# Headstage_Mainboard.net
KiCad netlist of a schematic drawn in Altium Designer
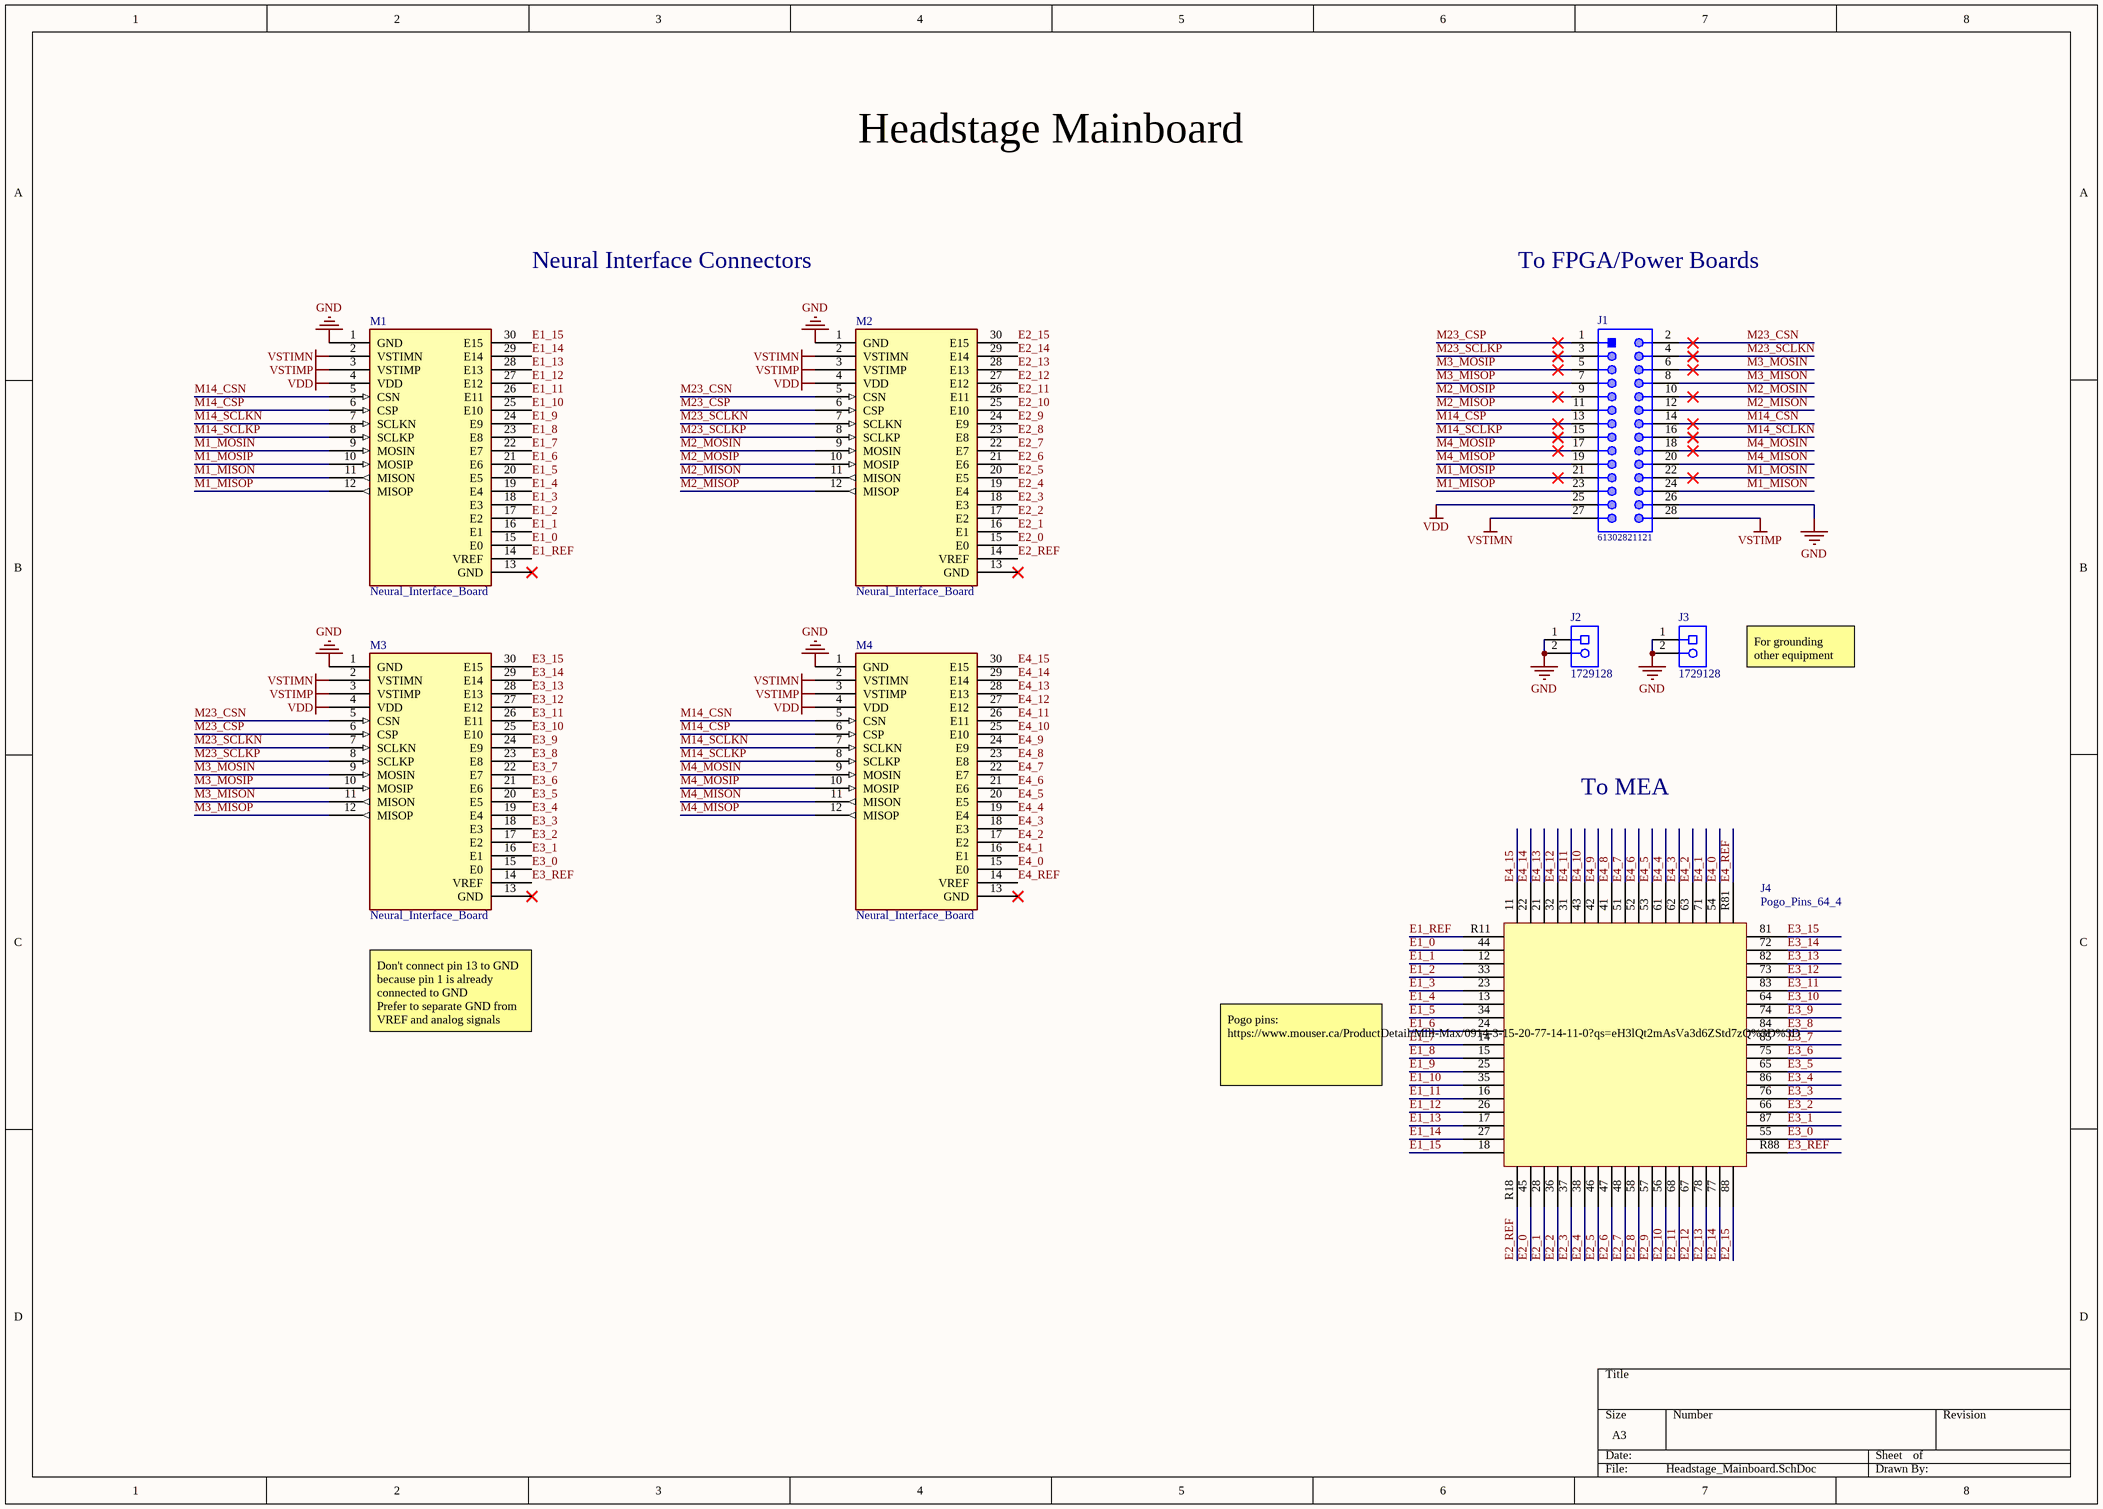
[diagram p0: Headstage_Mainboard.SchDoc]

(export (version "E")
  (design (tool "Eeschema 10.0.6"))
  (components
    (comp (ref "J1")
      (value "61302821121")
      (footprint "61302821121")
      (description "THT Vertical Pin Header WR-PHD, Pitch 2.54 mm, Dual Row, 28 pins")
      (fields (field (name "MANUFACTURER") "Wurth Elektronik") (field (name "PUBLISHER") "WurthElektronik"))
      (libsource (lib "Altium Content Vault") (part "WE-CN-2P-M-R28"))
    )
    (comp (ref "J2")
      (value "1729128")
      (footprint "PHOE-1729128-2_V")
      (description "PCB Terminal Block, 13.5 A, 400 V, 2-Pin THD, RoHS, Bulk")
      (fields (field (name "MANUFACTURER") "Phoenix Contact"))
      (libsource (lib "Altium Content Vault") (part "CN-2P-F-R2"))
    )
    (comp (ref "J3")
      (value "1729128")
      (footprint "PHOE-1729128-2_V")
      (description "PCB Terminal Block, 13.5 A, 400 V, 2-Pin THD, RoHS, Bulk")
      (fields (field (name "MANUFACTURER") "Phoenix Contact"))
      (libsource (lib "Altium Content Vault") (part "CN-2P-F-R2"))
    )
    (comp (ref "J4")
      (value "Pogo_Pins_64_4")
      (footprint "Pogo_Pins_64_4")
      (description "Pogo pins, 64 recording electrodes, 4 reference electrodes")
      (libsource (lib "OpenMEA") (part "Pogo_Pins_64_4"))
    )
    (comp (ref "M1")
      (value "Neural_Interface_Board")
      (footprint "Neural_Interface_Board")
      (libsource (lib "OpenMEA") (part "Neural_Interface_Board"))
    )
    (comp (ref "M2")
      (value "Neural_Interface_Board")
      (footprint "Neural_Interface_Board")
      (libsource (lib "OpenMEA") (part "Neural_Interface_Board"))
    )
    (comp (ref "M3")
      (value "Neural_Interface_Board")
      (footprint "Neural_Interface_Board")
      (libsource (lib "OpenMEA") (part "Neural_Interface_Board"))
    )
    (comp (ref "M4")
      (value "Neural_Interface_Board")
      (footprint "Neural_Interface_Board")
      (libsource (lib "OpenMEA") (part "Neural_Interface_Board"))
    )
  )
  (nets
    (net (code "1") (name "/E1_0") (class "Default")
      (node (ref "J4") (pin "44") (pintype "passive"))
      (node (ref "M1") (pin "15") (pinfunction "E0_15") (pintype "passive"))
    )
    (net (code "2") (name "/E1_1") (class "Default")
      (node (ref "J4") (pin "12") (pintype "passive"))
      (node (ref "M1") (pin "16") (pinfunction "E1_16") (pintype "passive"))
    )
    (net (code "3") (name "/E1_2") (class "Default")
      (node (ref "J4") (pin "33") (pintype "passive"))
      (node (ref "M1") (pin "17") (pinfunction "E2_17") (pintype "passive"))
    )
    (net (code "4") (name "/E1_3") (class "Default")
      (node (ref "J4") (pin "23") (pintype "passive"))
      (node (ref "M1") (pin "18") (pinfunction "E3_18") (pintype "passive"))
    )
    (net (code "5") (name "/E1_4") (class "Default")
      (node (ref "J4") (pin "13") (pintype "passive"))
      (node (ref "M1") (pin "19") (pinfunction "E4_19") (pintype "passive"))
    )
    (net (code "6") (name "/E1_5") (class "Default")
      (node (ref "J4") (pin "34") (pintype "passive"))
      (node (ref "M1") (pin "20") (pinfunction "E5_20") (pintype "passive"))
    )
    (net (code "7") (name "/E1_6") (class "Default")
      (node (ref "J4") (pin "24") (pintype "passive"))
      (node (ref "M1") (pin "21") (pinfunction "E6_21") (pintype "passive"))
    )
    (net (code "8") (name "/E1_7") (class "Default")
      (node (ref "J4") (pin "14") (pintype "passive"))
      (node (ref "M1") (pin "22") (pinfunction "E7_22") (pintype "passive"))
    )
    (net (code "9") (name "/E1_8") (class "Default")
      (node (ref "J4") (pin "15") (pintype "passive"))
      (node (ref "M1") (pin "23") (pinfunction "E8_23") (pintype "passive"))
    )
    (net (code "10") (name "/E1_9") (class "Default")
      (node (ref "J4") (pin "25") (pintype "passive"))
      (node (ref "M1") (pin "24") (pinfunction "E9_24") (pintype "passive"))
    )
    (net (code "11") (name "/E1_10") (class "Default")
      (node (ref "J4") (pin "35") (pintype "passive"))
      (node (ref "M1") (pin "25") (pinfunction "E10_25") (pintype "passive"))
    )
    (net (code "12") (name "/E1_11") (class "Default")
      (node (ref "J4") (pin "16") (pintype "passive"))
      (node (ref "M1") (pin "26") (pinfunction "E11_26") (pintype "passive"))
    )
    (net (code "13") (name "/E1_12") (class "Default")
      (node (ref "J4") (pin "26") (pintype "passive"))
      (node (ref "M1") (pin "27") (pinfunction "E12_27") (pintype "passive"))
    )
    (net (code "14") (name "/E1_13") (class "Default")
      (node (ref "J4") (pin "17") (pintype "passive"))
      (node (ref "M1") (pin "28") (pinfunction "E13_28") (pintype "passive"))
    )
    (net (code "15") (name "/E1_14") (class "Default")
      (node (ref "J4") (pin "27") (pintype "passive"))
      (node (ref "M1") (pin "29") (pinfunction "E14_29") (pintype "passive"))
    )
    (net (code "16") (name "/E1_15") (class "Default")
      (node (ref "J4") (pin "18") (pintype "passive"))
      (node (ref "M1") (pin "30") (pinfunction "E15_30") (pintype "passive"))
    )
    (net (code "17") (name "/E1_REF") (class "Default")
      (node (ref "J4") (pin "R11") (pintype "passive"))
      (node (ref "M1") (pin "14") (pinfunction "VREF_14") (pintype "passive"))
    )
    (net (code "18") (name "/E2_0") (class "Default")
      (node (ref "J4") (pin "45") (pintype "passive"))
      (node (ref "M2") (pin "15") (pinfunction "E0_15") (pintype "passive"))
    )
    (net (code "19") (name "/E2_1") (class "Default")
      (node (ref "J4") (pin "28") (pintype "passive"))
      (node (ref "M2") (pin "16") (pinfunction "E1_16") (pintype "passive"))
    )
    (net (code "20") (name "/E2_2") (class "Default")
      (node (ref "J4") (pin "36") (pintype "passive"))
      (node (ref "M2") (pin "17") (pinfunction "E2_17") (pintype "passive"))
    )
    (net (code "21") (name "/E2_3") (class "Default")
      (node (ref "J4") (pin "37") (pintype "passive"))
      (node (ref "M2") (pin "18") (pinfunction "E3_18") (pintype "passive"))
    )
    (net (code "22") (name "/E2_4") (class "Default")
      (node (ref "J4") (pin "38") (pintype "passive"))
      (node (ref "M2") (pin "19") (pinfunction "E4_19") (pintype "passive"))
    )
    (net (code "23") (name "/E2_5") (class "Default")
      (node (ref "J4") (pin "46") (pintype "passive"))
      (node (ref "M2") (pin "20") (pinfunction "E5_20") (pintype "passive"))
    )
    (net (code "24") (name "/E2_6") (class "Default")
      (node (ref "J4") (pin "47") (pintype "passive"))
      (node (ref "M2") (pin "21") (pinfunction "E6_21") (pintype "passive"))
    )
    (net (code "25") (name "/E2_7") (class "Default")
      (node (ref "J4") (pin "48") (pintype "passive"))
      (node (ref "M2") (pin "22") (pinfunction "E7_22") (pintype "passive"))
    )
    (net (code "26") (name "/E2_8") (class "Default")
      (node (ref "J4") (pin "58") (pintype "passive"))
      (node (ref "M2") (pin "23") (pinfunction "E8_23") (pintype "passive"))
    )
    (net (code "27") (name "/E2_9") (class "Default")
      (node (ref "J4") (pin "57") (pintype "passive"))
      (node (ref "M2") (pin "24") (pinfunction "E9_24") (pintype "passive"))
    )
    (net (code "28") (name "/E2_10") (class "Default")
      (node (ref "J4") (pin "56") (pintype "passive"))
      (node (ref "M2") (pin "25") (pinfunction "E10_25") (pintype "passive"))
    )
    (net (code "29") (name "/E2_11") (class "Default")
      (node (ref "J4") (pin "68") (pintype "passive"))
      (node (ref "M2") (pin "26") (pinfunction "E11_26") (pintype "passive"))
    )
    (net (code "30") (name "/E2_12") (class "Default")
      (node (ref "J4") (pin "67") (pintype "passive"))
      (node (ref "M2") (pin "27") (pinfunction "E12_27") (pintype "passive"))
    )
    (net (code "31") (name "/E2_13") (class "Default")
      (node (ref "J4") (pin "78") (pintype "passive"))
      (node (ref "M2") (pin "28") (pinfunction "E13_28") (pintype "passive"))
    )
    (net (code "32") (name "/E2_14") (class "Default")
      (node (ref "J4") (pin "77") (pintype "passive"))
      (node (ref "M2") (pin "29") (pinfunction "E14_29") (pintype "passive"))
    )
    (net (code "33") (name "/E2_15") (class "Default")
      (node (ref "J4") (pin "88") (pintype "passive"))
      (node (ref "M2") (pin "30") (pinfunction "E15_30") (pintype "passive"))
    )
    (net (code "34") (name "/E2_REF") (class "Default")
      (node (ref "J4") (pin "R18") (pintype "passive"))
      (node (ref "M2") (pin "14") (pinfunction "VREF_14") (pintype "passive"))
    )
    (net (code "35") (name "/E3_0") (class "Default")
      (node (ref "J4") (pin "55") (pintype "passive"))
      (node (ref "M3") (pin "15") (pinfunction "E0_15") (pintype "passive"))
    )
    (net (code "36") (name "/E3_1") (class "Default")
      (node (ref "J4") (pin "87") (pintype "passive"))
      (node (ref "M3") (pin "16") (pinfunction "E1_16") (pintype "passive"))
    )
    (net (code "37") (name "/E3_2") (class "Default")
      (node (ref "J4") (pin "66") (pintype "passive"))
      (node (ref "M3") (pin "17") (pinfunction "E2_17") (pintype "passive"))
    )
    (net (code "38") (name "/E3_3") (class "Default")
      (node (ref "J4") (pin "76") (pintype "passive"))
      (node (ref "M3") (pin "18") (pinfunction "E3_18") (pintype "passive"))
    )
    (net (code "39") (name "/E3_4") (class "Default")
      (node (ref "J4") (pin "86") (pintype "passive"))
      (node (ref "M3") (pin "19") (pinfunction "E4_19") (pintype "passive"))
    )
    (net (code "40") (name "/E3_5") (class "Default")
      (node (ref "J4") (pin "65") (pintype "passive"))
      (node (ref "M3") (pin "20") (pinfunction "E5_20") (pintype "passive"))
    )
    (net (code "41") (name "/E3_6") (class "Default")
      (node (ref "J4") (pin "75") (pintype "passive"))
      (node (ref "M3") (pin "21") (pinfunction "E6_21") (pintype "passive"))
    )
    (net (code "42") (name "/E3_7") (class "Default")
      (node (ref "J4") (pin "85") (pintype "passive"))
      (node (ref "M3") (pin "22") (pinfunction "E7_22") (pintype "passive"))
    )
    (net (code "43") (name "/E3_8") (class "Default")
      (node (ref "J4") (pin "84") (pintype "passive"))
      (node (ref "M3") (pin "23") (pinfunction "E8_23") (pintype "passive"))
    )
    (net (code "44") (name "/E3_9") (class "Default")
      (node (ref "J4") (pin "74") (pintype "passive"))
      (node (ref "M3") (pin "24") (pinfunction "E9_24") (pintype "passive"))
    )
    (net (code "45") (name "/E3_10") (class "Default")
      (node (ref "J4") (pin "64") (pintype "passive"))
      (node (ref "M3") (pin "25") (pinfunction "E10_25") (pintype "passive"))
    )
    (net (code "46") (name "/E3_11") (class "Default")
      (node (ref "J4") (pin "83") (pintype "passive"))
      (node (ref "M3") (pin "26") (pinfunction "E11_26") (pintype "passive"))
    )
    (net (code "47") (name "/E3_12") (class "Default")
      (node (ref "J4") (pin "73") (pintype "passive"))
      (node (ref "M3") (pin "27") (pinfunction "E12_27") (pintype "passive"))
    )
    (net (code "48") (name "/E3_13") (class "Default")
      (node (ref "J4") (pin "82") (pintype "passive"))
      (node (ref "M3") (pin "28") (pinfunction "E13_28") (pintype "passive"))
    )
    (net (code "49") (name "/E3_14") (class "Default")
      (node (ref "J4") (pin "72") (pintype "passive"))
      (node (ref "M3") (pin "29") (pinfunction "E14_29") (pintype "passive"))
    )
    (net (code "50") (name "/E3_15") (class "Default")
      (node (ref "J4") (pin "81") (pintype "passive"))
      (node (ref "M3") (pin "30") (pinfunction "E15_30") (pintype "passive"))
    )
    (net (code "51") (name "/E3_REF") (class "Default")
      (node (ref "J4") (pin "R88") (pintype "passive"))
      (node (ref "M3") (pin "14") (pinfunction "VREF_14") (pintype "passive"))
    )
    (net (code "52") (name "/E4_0") (class "Default")
      (node (ref "J4") (pin "54") (pintype "passive"))
      (node (ref "M4") (pin "15") (pinfunction "E0_15") (pintype "passive"))
    )
    (net (code "53") (name "/E4_1") (class "Default")
      (node (ref "J4") (pin "71") (pintype "passive"))
      (node (ref "M4") (pin "16") (pinfunction "E1_16") (pintype "passive"))
    )
    (net (code "54") (name "/E4_2") (class "Default")
      (node (ref "J4") (pin "63") (pintype "passive"))
      (node (ref "M4") (pin "17") (pinfunction "E2_17") (pintype "passive"))
    )
    (net (code "55") (name "/E4_3") (class "Default")
      (node (ref "J4") (pin "62") (pintype "passive"))
      (node (ref "M4") (pin "18") (pinfunction "E3_18") (pintype "passive"))
    )
    (net (code "56") (name "/E4_4") (class "Default")
      (node (ref "J4") (pin "61") (pintype "passive"))
      (node (ref "M4") (pin "19") (pinfunction "E4_19") (pintype "passive"))
    )
    (net (code "57") (name "/E4_5") (class "Default")
      (node (ref "J4") (pin "53") (pintype "passive"))
      (node (ref "M4") (pin "20") (pinfunction "E5_20") (pintype "passive"))
    )
    (net (code "58") (name "/E4_6") (class "Default")
      (node (ref "J4") (pin "52") (pintype "passive"))
      (node (ref "M4") (pin "21") (pinfunction "E6_21") (pintype "passive"))
    )
    (net (code "59") (name "/E4_7") (class "Default")
      (node (ref "J4") (pin "51") (pintype "passive"))
      (node (ref "M4") (pin "22") (pinfunction "E7_22") (pintype "passive"))
    )
    (net (code "60") (name "/E4_8") (class "Default")
      (node (ref "J4") (pin "41") (pintype "passive"))
      (node (ref "M4") (pin "23") (pinfunction "E8_23") (pintype "passive"))
    )
    (net (code "61") (name "/E4_9") (class "Default")
      (node (ref "J4") (pin "42") (pintype "passive"))
      (node (ref "M4") (pin "24") (pinfunction "E9_24") (pintype "passive"))
    )
    (net (code "62") (name "/E4_10") (class "Default")
      (node (ref "J4") (pin "43") (pintype "passive"))
      (node (ref "M4") (pin "25") (pinfunction "E10_25") (pintype "passive"))
    )
    (net (code "63") (name "/E4_11") (class "Default")
      (node (ref "J4") (pin "31") (pintype "passive"))
      (node (ref "M4") (pin "26") (pinfunction "E11_26") (pintype "passive"))
    )
    (net (code "64") (name "/E4_12") (class "Default")
      (node (ref "J4") (pin "32") (pintype "passive"))
      (node (ref "M4") (pin "27") (pinfunction "E12_27") (pintype "passive"))
    )
    (net (code "65") (name "/E4_13") (class "Default")
      (node (ref "J4") (pin "21") (pintype "passive"))
      (node (ref "M4") (pin "28") (pinfunction "E13_28") (pintype "passive"))
    )
    (net (code "66") (name "/E4_14") (class "Default")
      (node (ref "J4") (pin "22") (pintype "passive"))
      (node (ref "M4") (pin "29") (pinfunction "E14_29") (pintype "passive"))
    )
    (net (code "67") (name "/E4_15") (class "Default")
      (node (ref "J4") (pin "11") (pintype "passive"))
      (node (ref "M4") (pin "30") (pinfunction "E15_30") (pintype "passive"))
    )
    (net (code "68") (name "/E4_REF") (class "Default")
      (node (ref "J4") (pin "R81") (pintype "passive"))
      (node (ref "M4") (pin "14") (pinfunction "VREF_14") (pintype "passive"))
    )
    (net (code "69") (name "/M1_MISON") (class "Default")
      (node (ref "J1") (pin "24") (pinfunction "24_24") (pintype "passive"))
      (node (ref "M1") (pin "11") (pinfunction "MISON_11") (pintype "output"))
    )
    (net (code "70") (name "/M1_MISOP") (class "Default")
      (node (ref "J1") (pin "23") (pinfunction "23_23") (pintype "passive"))
      (node (ref "M1") (pin "12") (pinfunction "MISOP_12") (pintype "output"))
    )
    (net (code "71") (name "/M1_MOSIN") (class "Default")
      (node (ref "J1") (pin "22") (pinfunction "22_22") (pintype "passive"))
      (node (ref "M1") (pin "9") (pinfunction "MOSIN_9") (pintype "input"))
    )
    (net (code "72") (name "/M1_MOSIP") (class "Default")
      (node (ref "J1") (pin "21") (pinfunction "21_21") (pintype "passive"))
      (node (ref "M1") (pin "10") (pinfunction "MOSIP_10") (pintype "input"))
    )
    (net (code "73") (name "/M2_MISON") (class "Default")
      (node (ref "J1") (pin "12") (pinfunction "12_12") (pintype "passive"))
      (node (ref "M2") (pin "11") (pinfunction "MISON_11") (pintype "output"))
    )
    (net (code "74") (name "/M2_MISOP") (class "Default")
      (node (ref "J1") (pin "11") (pinfunction "11_11") (pintype "passive"))
      (node (ref "M2") (pin "12") (pinfunction "MISOP_12") (pintype "output"))
    )
    (net (code "75") (name "/M2_MOSIN") (class "Default")
      (node (ref "J1") (pin "10") (pinfunction "10_10") (pintype "passive"))
      (node (ref "M2") (pin "9") (pinfunction "MOSIN_9") (pintype "input"))
    )
    (net (code "76") (name "/M2_MOSIP") (class "Default")
      (node (ref "J1") (pin "9") (pinfunction "9_9") (pintype "passive"))
      (node (ref "M2") (pin "10") (pinfunction "MOSIP_10") (pintype "input"))
    )
    (net (code "77") (name "/M3_MISON") (class "Default")
      (node (ref "J1") (pin "8") (pinfunction "8_8") (pintype "passive"))
      (node (ref "M3") (pin "11") (pinfunction "MISON_11") (pintype "output"))
    )
    (net (code "78") (name "/M3_MISOP") (class "Default")
      (node (ref "J1") (pin "7") (pinfunction "7_7") (pintype "passive"))
      (node (ref "M3") (pin "12") (pinfunction "MISOP_12") (pintype "output"))
    )
    (net (code "79") (name "/M3_MOSIN") (class "Default")
      (node (ref "J1") (pin "6") (pinfunction "6_6") (pintype "passive"))
      (node (ref "M3") (pin "9") (pinfunction "MOSIN_9") (pintype "input"))
    )
    (net (code "80") (name "/M3_MOSIP") (class "Default")
      (node (ref "J1") (pin "5") (pinfunction "5_5") (pintype "passive"))
      (node (ref "M3") (pin "10") (pinfunction "MOSIP_10") (pintype "input"))
    )
    (net (code "81") (name "/M4_MISON") (class "Default")
      (node (ref "J1") (pin "20") (pinfunction "20_20") (pintype "passive"))
      (node (ref "M4") (pin "11") (pinfunction "MISON_11") (pintype "output"))
    )
    (net (code "82") (name "/M4_MISOP") (class "Default")
      (node (ref "J1") (pin "19") (pinfunction "19_19") (pintype "passive"))
      (node (ref "M4") (pin "12") (pinfunction "MISOP_12") (pintype "output"))
    )
    (net (code "83") (name "/M4_MOSIN") (class "Default")
      (node (ref "J1") (pin "18") (pinfunction "18_18") (pintype "passive"))
      (node (ref "M4") (pin "9") (pinfunction "MOSIN_9") (pintype "input"))
    )
    (net (code "84") (name "/M4_MOSIP") (class "Default")
      (node (ref "J1") (pin "17") (pinfunction "17_17") (pintype "passive"))
      (node (ref "M4") (pin "10") (pinfunction "MOSIP_10") (pintype "input"))
    )
    (net (code "85") (name "/M14_CSN") (class "Default")
      (node (ref "J1") (pin "14") (pinfunction "14_14") (pintype "passive"))
      (node (ref "M1") (pin "5") (pinfunction "CSN_5") (pintype "input"))
      (node (ref "M4") (pin "5") (pinfunction "CSN_5") (pintype "input"))
    )
    (net (code "86") (name "/M14_CSP") (class "Default")
      (node (ref "J1") (pin "13") (pinfunction "13_13") (pintype "passive"))
      (node (ref "M1") (pin "6") (pinfunction "CSP_6") (pintype "input"))
      (node (ref "M4") (pin "6") (pinfunction "CSP_6") (pintype "input"))
    )
    (net (code "87") (name "/M14_SCLKN") (class "Default")
      (node (ref "J1") (pin "16") (pinfunction "16_16") (pintype "passive"))
      (node (ref "M1") (pin "7") (pinfunction "SCLKN_7") (pintype "input"))
      (node (ref "M4") (pin "7") (pinfunction "SCLKN_7") (pintype "input"))
    )
    (net (code "88") (name "/M14_SCLKP") (class "Default")
      (node (ref "J1") (pin "15") (pinfunction "15_15") (pintype "passive"))
      (node (ref "M1") (pin "8") (pinfunction "SCLKP_8") (pintype "input"))
      (node (ref "M4") (pin "8") (pinfunction "SCLKP_8") (pintype "input"))
    )
    (net (code "89") (name "/M23_CSN") (class "Default")
      (node (ref "J1") (pin "2") (pinfunction "2_2") (pintype "passive"))
      (node (ref "M2") (pin "5") (pinfunction "CSN_5") (pintype "input"))
      (node (ref "M3") (pin "5") (pinfunction "CSN_5") (pintype "input"))
    )
    (net (code "90") (name "/M23_CSP") (class "Default")
      (node (ref "J1") (pin "1") (pinfunction "1_1") (pintype "passive"))
      (node (ref "M2") (pin "6") (pinfunction "CSP_6") (pintype "input"))
      (node (ref "M3") (pin "6") (pinfunction "CSP_6") (pintype "input"))
    )
    (net (code "91") (name "/M23_SCLKN") (class "Default")
      (node (ref "J1") (pin "4") (pinfunction "4_4") (pintype "passive"))
      (node (ref "M2") (pin "7") (pinfunction "SCLKN_7") (pintype "input"))
      (node (ref "M3") (pin "7") (pinfunction "SCLKN_7") (pintype "input"))
    )
    (net (code "92") (name "/M23_SCLKP") (class "Default")
      (node (ref "J1") (pin "3") (pinfunction "3_3") (pintype "passive"))
      (node (ref "M2") (pin "8") (pinfunction "SCLKP_8") (pintype "input"))
      (node (ref "M3") (pin "8") (pinfunction "SCLKP_8") (pintype "input"))
    )
    (net (code "93") (name "GND") (class "Default")
      (node (ref "J1") (pin "26") (pinfunction "26_26") (pintype "passive"))
      (node (ref "J2") (pin "1") (pinfunction "1_1") (pintype "passive"))
      (node (ref "J2") (pin "2") (pinfunction "2_2") (pintype "passive"))
      (node (ref "J3") (pin "1") (pinfunction "1_1") (pintype "passive"))
      (node (ref "J3") (pin "2") (pinfunction "2_2") (pintype "passive"))
      (node (ref "M1") (pin "1") (pinfunction "GND_1") (pintype "power_in"))
      (node (ref "M2") (pin "1") (pinfunction "GND_1") (pintype "power_in"))
      (node (ref "M3") (pin "1") (pinfunction "GND_1") (pintype "power_in"))
      (node (ref "M4") (pin "1") (pinfunction "GND_1") (pintype "power_in"))
    )
    (net (code "94") (name "VDD") (class "Default")
      (node (ref "J1") (pin "25") (pinfunction "25_25") (pintype "passive"))
      (node (ref "M1") (pin "4") (pinfunction "VDD_4") (pintype "power_in"))
      (node (ref "M2") (pin "4") (pinfunction "VDD_4") (pintype "power_in"))
      (node (ref "M3") (pin "4") (pinfunction "VDD_4") (pintype "power_in"))
      (node (ref "M4") (pin "4") (pinfunction "VDD_4") (pintype "power_in"))
    )
    (net (code "95") (name "VSTIMN") (class "Default")
      (node (ref "J1") (pin "27") (pinfunction "27_27") (pintype "passive"))
      (node (ref "M1") (pin "2") (pinfunction "VSTIMN_2") (pintype "power_in"))
      (node (ref "M2") (pin "2") (pinfunction "VSTIMN_2") (pintype "power_in"))
      (node (ref "M3") (pin "2") (pinfunction "VSTIMN_2") (pintype "power_in"))
      (node (ref "M4") (pin "2") (pinfunction "VSTIMN_2") (pintype "power_in"))
    )
    (net (code "96") (name "VSTIMP") (class "Default")
      (node (ref "J1") (pin "28") (pinfunction "28_28") (pintype "passive"))
      (node (ref "M1") (pin "3") (pinfunction "VSTIMP_3") (pintype "power_in"))
      (node (ref "M2") (pin "3") (pinfunction "VSTIMP_3") (pintype "power_in"))
      (node (ref "M3") (pin "3") (pinfunction "VSTIMP_3") (pintype "power_in"))
      (node (ref "M4") (pin "3") (pinfunction "VSTIMP_3") (pintype "power_in"))
    )
    (net (code "97") (name "unconnected-(M1-GND-Pad13)") (class "Default")
      (node (ref "M1") (pin "13") (pinfunction "GND_13") (pintype "power_in+no_connect"))
    )
    (net (code "98") (name "unconnected-(M2-GND-Pad13)") (class "Default")
      (node (ref "M2") (pin "13") (pinfunction "GND_13") (pintype "power_in+no_connect"))
    )
    (net (code "99") (name "unconnected-(M3-GND-Pad13)") (class "Default")
      (node (ref "M3") (pin "13") (pinfunction "GND_13") (pintype "power_in+no_connect"))
    )
    (net (code "100") (name "unconnected-(M4-GND-Pad13)") (class "Default")
      (node (ref "M4") (pin "13") (pinfunction "GND_13") (pintype "power_in+no_connect"))
    )
  )
)
